# USB_stick.net
KiCad netlist of a schematic drawn in EAGLE
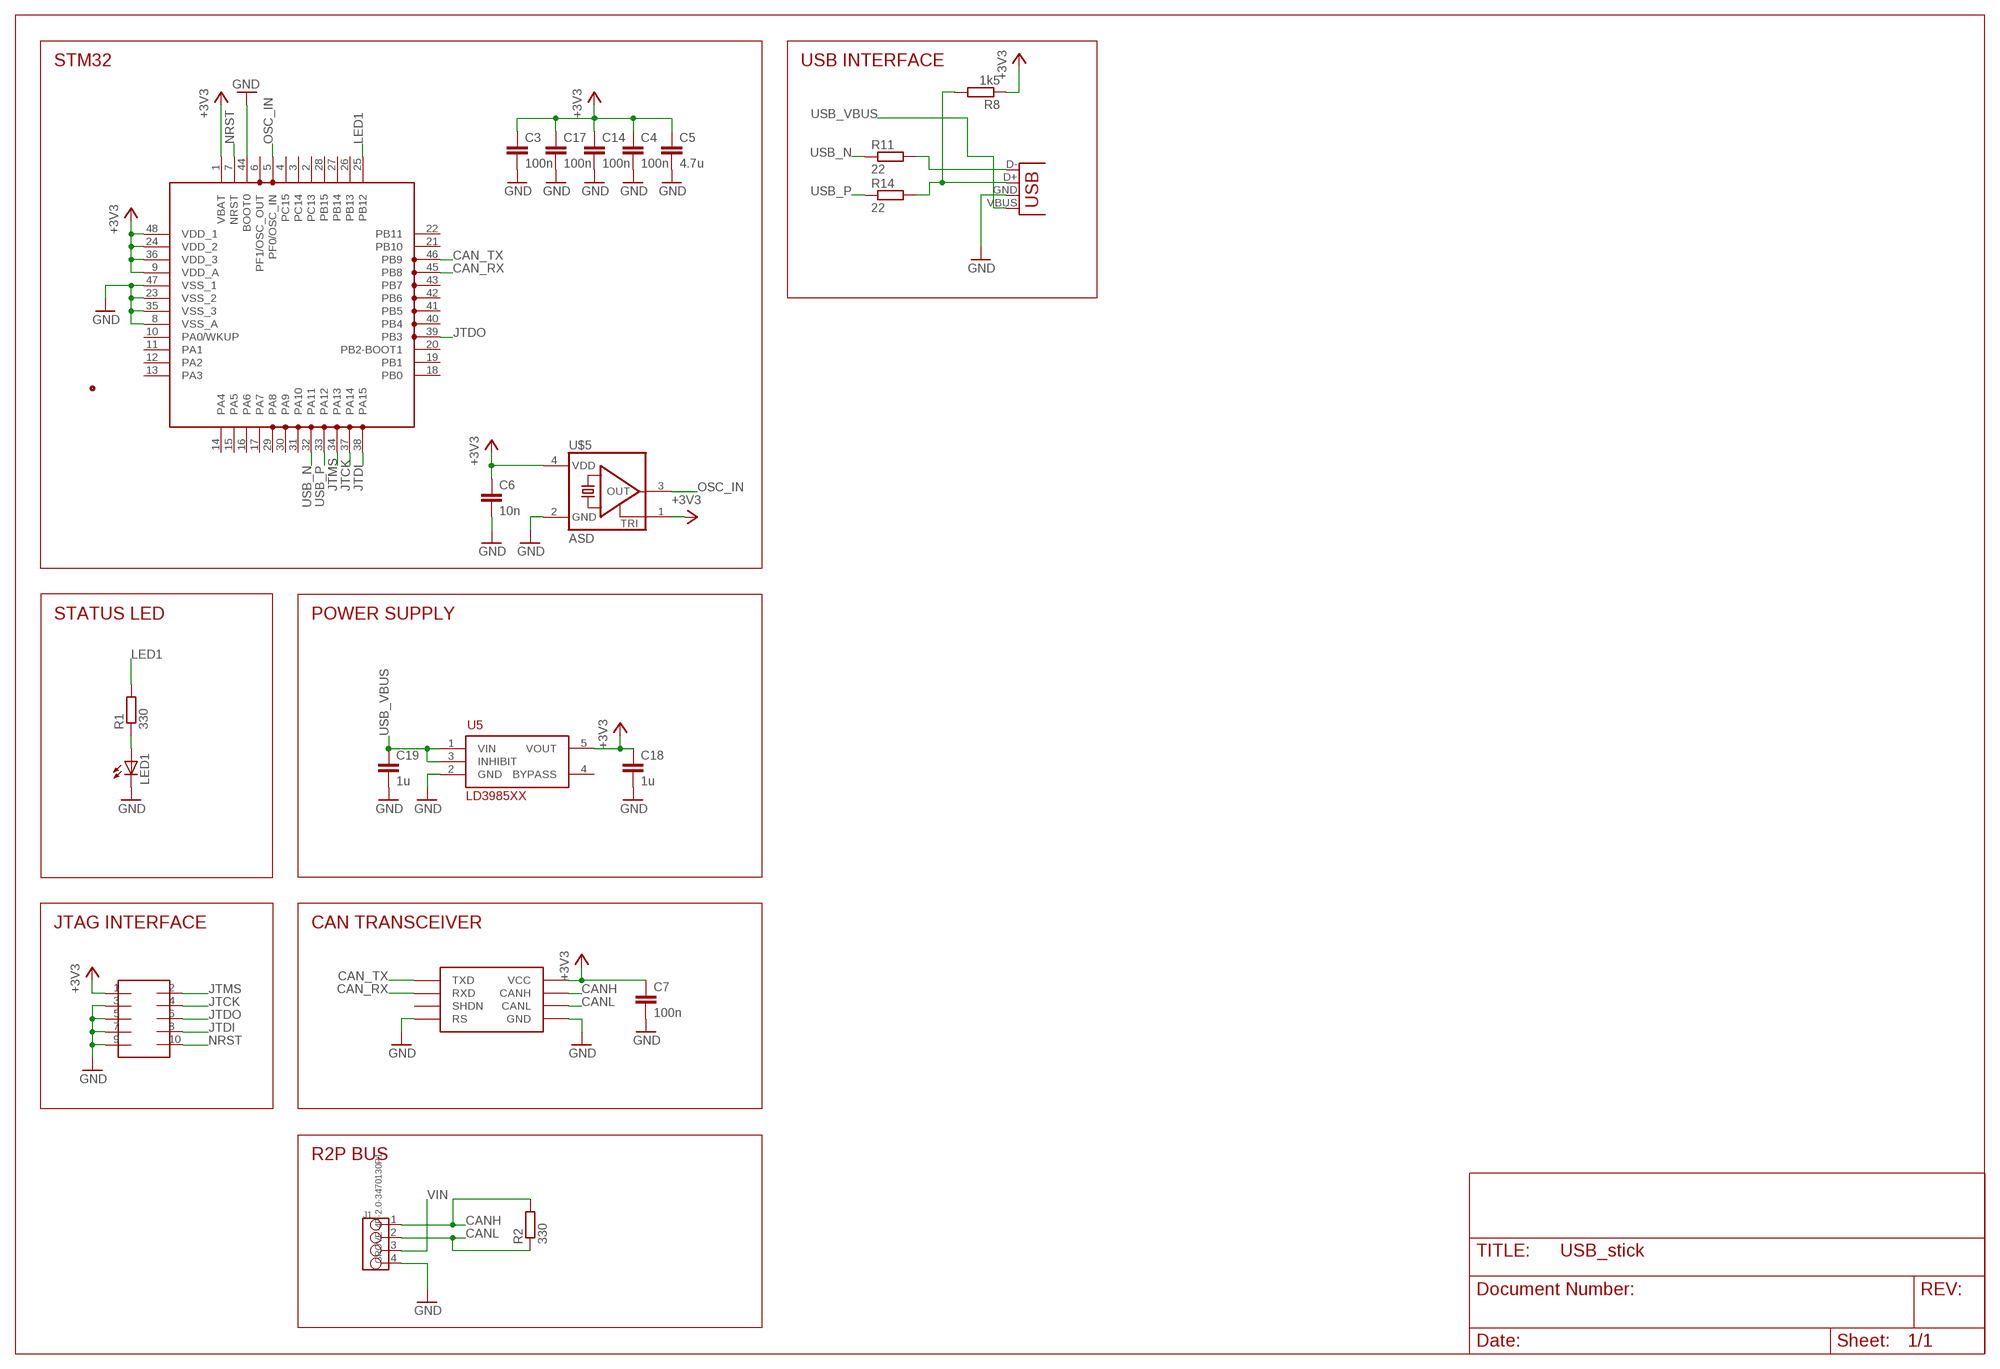
[diagram p0: schematic, sheet 1]

(export (version "E")
  (design (tool "Eeschema 10.0.6"))
  (components
    (comp (ref "C3")
      (value "100n")
      (footprint "eagle-import:C0603")
      (libsource (lib "eagle-import") (part "C-EUC0603"))
    )
    (comp (ref "C4")
      (value "100n")
      (footprint "eagle-import:C0603")
      (libsource (lib "eagle-import") (part "C-EUC0603"))
    )
    (comp (ref "C5")
      (value "4.7u")
      (footprint "eagle-import:C0805")
      (libsource (lib "eagle-import") (part "C-EUC0805"))
    )
    (comp (ref "C6")
      (value "10n")
      (footprint "eagle-import:C0603")
      (libsource (lib "eagle-import") (part "C-EUC0603"))
    )
    (comp (ref "C7")
      (value "100n")
      (footprint "eagle-import:C0603")
      (libsource (lib "eagle-import") (part "C-EUC0603"))
    )
    (comp (ref "C14")
      (value "100n")
      (footprint "eagle-import:C0603")
      (libsource (lib "eagle-import") (part "C-EUC0603"))
    )
    (comp (ref "C17")
      (value "100n")
      (footprint "eagle-import:C0603")
      (libsource (lib "eagle-import") (part "C-EUC0603"))
    )
    (comp (ref "C18")
      (value "1u")
      (footprint "eagle-import:C0603")
      (libsource (lib "eagle-import") (part "C-EUC0603"))
    )
    (comp (ref "C19")
      (value "1u")
      (footprint "eagle-import:C0603")
      (libsource (lib "eagle-import") (part "C-EUC0603"))
    )
    (comp (ref "J1")
      (value "GROVE-4P-2.0-3470130P1")
      (footprint "eagle-import:4P-2.0")
      (libsource (lib "eagle-import") (part "GROVE-4P-2.0-3470130P1"))
    )
    (comp (ref "JP1")
      (value "USB-A-H")
      (footprint "eagle-import:USB-A-H")
      (libsource (lib "eagle-import") (part "USB-A-H"))
    )
    (comp (ref "LED1")
      (value "LEDCHIPLED_0805")
      (footprint "eagle-import:CHIPLED_0805")
      (libsource (lib "eagle-import") (part "LEDCHIPLED_0805"))
    )
    (comp (ref "R1")
      (value "330")
      (footprint "eagle-import:R0603")
      (libsource (lib "eagle-import") (part "R0603"))
    )
    (comp (ref "R2")
      (value "330")
      (footprint "eagle-import:R0603")
      (libsource (lib "eagle-import") (part "R0603"))
    )
    (comp (ref "R8")
      (value "1k5")
      (footprint "eagle-import:R0603")
      (libsource (lib "eagle-import") (part "R0603"))
    )
    (comp (ref "R11")
      (value "22")
      (footprint "eagle-import:R0603")
      (libsource (lib "eagle-import") (part "R0603"))
    )
    (comp (ref "R14")
      (value "22")
      (footprint "eagle-import:R0603")
      (libsource (lib "eagle-import") (part "R0603"))
    )
    (comp (ref "SOT1")
      (value "MAX3051EKA")
      (footprint "eagle-import:SOT23-8L")
      (libsource (lib "eagle-import") (part "MAX3051EKA"))
    )
    (comp (ref "U$4")
      (value "FTSH-105TH")
      (footprint "eagle-import:FTSH-105-TH")
      (libsource (lib "eagle-import") (part "FTSH-105TH"))
    )
    (comp (ref "U$5")
      (value "ASD")
      (footprint "eagle-import:2.5X2")
      (libsource (lib "eagle-import") (part "ASD"))
    )
    (comp (ref "U$6")
      (value "STM32F303C")
      (footprint "eagle-import:LQFP48")
      (libsource (lib "eagle-import") (part "STM32F303C"))
    )
    (comp (ref "U5")
      (value "LD3985XX")
      (footprint "eagle-import:SOT23-5L")
      (libsource (lib "eagle-import") (part "LD3985XX"))
    )
  )
  (nets
    (net (code "1") (name "+3V3") (class "Default")
      (node (ref "C14") (pin "1") (pinfunction "1_1") (pintype "passive"))
      (node (ref "C17") (pin "1") (pinfunction "1_1") (pintype "passive"))
      (node (ref "C18") (pin "1") (pinfunction "1_1") (pintype "passive"))
      (node (ref "C3") (pin "1") (pinfunction "1_1") (pintype "passive"))
      (node (ref "C4") (pin "1") (pinfunction "1_1") (pintype "passive"))
      (node (ref "C5") (pin "1") (pinfunction "1_1") (pintype "passive"))
      (node (ref "C6") (pin "1") (pinfunction "1_1") (pintype "passive"))
      (node (ref "C7") (pin "1") (pinfunction "1_1") (pintype "passive"))
      (node (ref "R8") (pin "1") (pinfunction "1_1") (pintype "passive"))
      (node (ref "SOT1") (pin "3") (pinfunction "VCC_3") (pintype "bidirectional"))
      (node (ref "U$4") (pin "1") (pinfunction "P$1_1") (pintype "bidirectional"))
      (node (ref "U$5") (pin "1") (pinfunction "TRI_1") (pintype "input"))
      (node (ref "U$5") (pin "4") (pinfunction "VDD_4") (pintype "power_in"))
      (node (ref "U$6") (pin "1") (pinfunction "VBAT_1") (pintype "bidirectional"))
      (node (ref "U$6") (pin "24") (pinfunction "VDD_2_24") (pintype "bidirectional"))
      (node (ref "U$6") (pin "36") (pinfunction "VDD_3_36") (pintype "bidirectional"))
      (node (ref "U$6") (pin "48") (pinfunction "VDD_1_48") (pintype "bidirectional"))
      (node (ref "U$6") (pin "9") (pinfunction "VDD_A_9") (pintype "bidirectional"))
      (node (ref "U5") (pin "5") (pinfunction "VOUT_5") (pintype "bidirectional"))
    )
    (net (code "2") (name "/CANH") (class "Default")
      (node (ref "J1") (pin "1") (pinfunction "1_1") (pintype "bidirectional"))
      (node (ref "R2") (pin "2") (pinfunction "2_2") (pintype "passive"))
      (node (ref "SOT1") (pin "7") (pinfunction "CANH_7") (pintype "bidirectional"))
    )
    (net (code "3") (name "/CANL") (class "Default")
      (node (ref "J1") (pin "2") (pinfunction "2_2") (pintype "bidirectional"))
      (node (ref "R2") (pin "1") (pinfunction "1_1") (pintype "passive"))
      (node (ref "SOT1") (pin "6") (pinfunction "CANL_6") (pintype "bidirectional"))
    )
    (net (code "4") (name "/CAN_RX") (class "Default")
      (node (ref "SOT1") (pin "4") (pinfunction "RXD_4") (pintype "bidirectional"))
      (node (ref "U$6") (pin "45") (pinfunction "PB8_45") (pintype "bidirectional"))
    )
    (net (code "5") (name "/CAN_TX") (class "Default")
      (node (ref "SOT1") (pin "1") (pinfunction "TXD_1") (pintype "bidirectional"))
      (node (ref "U$6") (pin "46") (pinfunction "PB9_46") (pintype "bidirectional"))
    )
    (net (code "6") (name "/JTCK") (class "Default")
      (node (ref "U$4") (pin "4") (pinfunction "P$4_4") (pintype "bidirectional"))
      (node (ref "U$6") (pin "37") (pinfunction "PA14_37") (pintype "bidirectional"))
    )
    (net (code "7") (name "/JTDI") (class "Default")
      (node (ref "U$4") (pin "8") (pinfunction "P$8_8") (pintype "bidirectional"))
      (node (ref "U$6") (pin "38") (pinfunction "PA15_38") (pintype "bidirectional"))
    )
    (net (code "8") (name "/JTDO") (class "Default")
      (node (ref "U$4") (pin "6") (pinfunction "P$6_6") (pintype "bidirectional"))
      (node (ref "U$6") (pin "39") (pinfunction "PB3_39") (pintype "bidirectional"))
    )
    (net (code "9") (name "/JTMS") (class "Default")
      (node (ref "U$4") (pin "2") (pinfunction "P$2_2") (pintype "bidirectional"))
      (node (ref "U$6") (pin "34") (pinfunction "PA13_34") (pintype "bidirectional"))
    )
    (net (code "10") (name "/LED1") (class "Default")
      (node (ref "R1") (pin "2") (pinfunction "2_2") (pintype "passive"))
      (node (ref "U$6") (pin "25") (pinfunction "PB12_25") (pintype "bidirectional"))
    )
    (net (code "11") (name "/NRST") (class "Default")
      (node (ref "U$4") (pin "10") (pinfunction "P$10_10") (pintype "bidirectional"))
      (node (ref "U$6") (pin "7") (pinfunction "NRST_7") (pintype "bidirectional"))
    )
    (net (code "12") (name "/OSC_IN") (class "Default")
      (node (ref "U$5") (pin "3") (pinfunction "OUT_3") (pintype "output"))
      (node (ref "U$6") (pin "5") (pinfunction "PF0/OSC_IN_5") (pintype "bidirectional"))
    )
    (net (code "13") (name "/USB_N") (class "Default")
      (node (ref "R11") (pin "1") (pinfunction "1_1") (pintype "passive"))
      (node (ref "U$6") (pin "32") (pinfunction "PA11_32") (pintype "bidirectional"))
    )
    (net (code "14") (name "/USB_P") (class "Default")
      (node (ref "R14") (pin "1") (pinfunction "1_1") (pintype "passive"))
      (node (ref "U$6") (pin "33") (pinfunction "PA12_33") (pintype "bidirectional"))
    )
    (net (code "15") (name "/USB_VBUS") (class "Default")
      (node (ref "C19") (pin "1") (pinfunction "1_1") (pintype "passive"))
      (node (ref "JP1") (pin "VBUS") (pinfunction "GND_VBUS") (pintype "bidirectional"))
      (node (ref "U5") (pin "1") (pinfunction "VIN_1") (pintype "bidirectional"))
      (node (ref "U5") (pin "3") (pinfunction "INHIBIT_3") (pintype "bidirectional"))
    )
    (net (code "16") (name "/VIN") (class "Default")
      (node (ref "J1") (pin "3") (pinfunction "3_3") (pintype "bidirectional"))
    )
    (net (code "17") (name "GND") (class "Default")
      (node (ref "C14") (pin "2") (pinfunction "2_2") (pintype "passive"))
      (node (ref "C17") (pin "2") (pinfunction "2_2") (pintype "passive"))
      (node (ref "C18") (pin "2") (pinfunction "2_2") (pintype "passive"))
      (node (ref "C19") (pin "2") (pinfunction "2_2") (pintype "passive"))
      (node (ref "C3") (pin "2") (pinfunction "2_2") (pintype "passive"))
      (node (ref "C4") (pin "2") (pinfunction "2_2") (pintype "passive"))
      (node (ref "C5") (pin "2") (pinfunction "2_2") (pintype "passive"))
      (node (ref "C6") (pin "2") (pinfunction "2_2") (pintype "passive"))
      (node (ref "C7") (pin "2") (pinfunction "2_2") (pintype "passive"))
      (node (ref "J1") (pin "4") (pinfunction "4_4") (pintype "bidirectional"))
      (node (ref "JP1") (pin "GND") (pinfunction "VBUS_GND") (pintype "bidirectional"))
      (node (ref "LED1") (pin "C") (pinfunction "C_C") (pintype "passive"))
      (node (ref "SOT1") (pin "2") (pinfunction "GND_2") (pintype "bidirectional"))
      (node (ref "SOT1") (pin "8") (pinfunction "RS_8") (pintype "bidirectional"))
      (node (ref "U$4") (pin "3") (pinfunction "P$3_3") (pintype "bidirectional"))
      (node (ref "U$4") (pin "5") (pinfunction "P$5_5") (pintype "bidirectional"))
      (node (ref "U$4") (pin "7") (pinfunction "P$7_7") (pintype "bidirectional"))
      (node (ref "U$4") (pin "9") (pinfunction "P$9_9") (pintype "bidirectional"))
      (node (ref "U$5") (pin "2") (pinfunction "GND_2") (pintype "power_in"))
      (node (ref "U$6") (pin "23") (pinfunction "VSS_2_23") (pintype "bidirectional"))
      (node (ref "U$6") (pin "35") (pinfunction "VSS_3_35") (pintype "bidirectional"))
      (node (ref "U$6") (pin "44") (pinfunction "BOOT0_44") (pintype "bidirectional"))
      (node (ref "U$6") (pin "47") (pinfunction "VSS_1_47") (pintype "bidirectional"))
      (node (ref "U$6") (pin "8") (pinfunction "VSS_A_8") (pintype "bidirectional"))
      (node (ref "U5") (pin "2") (pinfunction "GND_2") (pintype "bidirectional"))
    )
    (net (code "18") (name "Net-(JP1-D+)") (class "Default")
      (node (ref "JP1") (pin "D-") (pinfunction "D+_D-") (pintype "bidirectional"))
      (node (ref "R11") (pin "2") (pinfunction "2_2") (pintype "passive"))
    )
    (net (code "19") (name "Net-(JP1-D-)") (class "Default")
      (node (ref "JP1") (pin "D+") (pinfunction "D-_D+") (pintype "bidirectional"))
      (node (ref "R14") (pin "2") (pinfunction "2_2") (pintype "passive"))
      (node (ref "R8") (pin "2") (pinfunction "2_2") (pintype "passive"))
    )
    (net (code "20") (name "Net-(LED1-PadA)") (class "Default")
      (node (ref "LED1") (pin "A") (pinfunction "A_A") (pintype "passive"))
      (node (ref "R1") (pin "1") (pinfunction "1_1") (pintype "passive"))
    )
    (net (code "21") (name "unconnected-(SOT1-SHDN-Pad5)") (class "Default")
      (node (ref "SOT1") (pin "5") (pinfunction "SHDN_5") (pintype "bidirectional"))
    )
    (net (code "22") (name "unconnected-(U$6-PA0{slash}WKUP-Pad10)") (class "Default")
      (node (ref "U$6") (pin "10") (pinfunction "PA0/WKUP_10") (pintype "bidirectional"))
    )
    (net (code "23") (name "unconnected-(U$6-PA1-Pad11)") (class "Default")
      (node (ref "U$6") (pin "11") (pinfunction "PA1_11") (pintype "bidirectional"))
    )
    (net (code "24") (name "unconnected-(U$6-PA2-Pad12)") (class "Default")
      (node (ref "U$6") (pin "12") (pinfunction "PA2_12") (pintype "bidirectional"))
    )
    (net (code "25") (name "unconnected-(U$6-PA3-Pad13)") (class "Default")
      (node (ref "U$6") (pin "13") (pinfunction "PA3_13") (pintype "bidirectional"))
    )
    (net (code "26") (name "unconnected-(U$6-PA4-Pad14)") (class "Default")
      (node (ref "U$6") (pin "14") (pinfunction "PA4_14") (pintype "bidirectional"))
    )
    (net (code "27") (name "unconnected-(U$6-PA5-Pad15)") (class "Default")
      (node (ref "U$6") (pin "15") (pinfunction "PA5_15") (pintype "bidirectional"))
    )
    (net (code "28") (name "unconnected-(U$6-PA6-Pad16)") (class "Default")
      (node (ref "U$6") (pin "16") (pinfunction "PA6_16") (pintype "bidirectional"))
    )
    (net (code "29") (name "unconnected-(U$6-PA7-Pad17)") (class "Default")
      (node (ref "U$6") (pin "17") (pinfunction "PA7_17") (pintype "bidirectional"))
    )
    (net (code "30") (name "unconnected-(U$6-PA8-Pad29)") (class "Default")
      (node (ref "U$6") (pin "29") (pinfunction "PA8_29") (pintype "bidirectional"))
    )
    (net (code "31") (name "unconnected-(U$6-PA9-Pad30)") (class "Default")
      (node (ref "U$6") (pin "30") (pinfunction "PA9_30") (pintype "bidirectional"))
    )
    (net (code "32") (name "unconnected-(U$6-PA10-Pad31)") (class "Default")
      (node (ref "U$6") (pin "31") (pinfunction "PA10_31") (pintype "bidirectional"))
    )
    (net (code "33") (name "unconnected-(U$6-PB0-Pad18)") (class "Default")
      (node (ref "U$6") (pin "18") (pinfunction "PB0_18") (pintype "bidirectional"))
    )
    (net (code "34") (name "unconnected-(U$6-PB1-Pad19)") (class "Default")
      (node (ref "U$6") (pin "19") (pinfunction "PB1_19") (pintype "bidirectional"))
    )
    (net (code "35") (name "unconnected-(U$6-PB2-BOOT1-Pad20)") (class "Default")
      (node (ref "U$6") (pin "20") (pinfunction "PB2-BOOT1_20") (pintype "bidirectional"))
    )
    (net (code "36") (name "unconnected-(U$6-PB4-Pad40)") (class "Default")
      (node (ref "U$6") (pin "40") (pinfunction "PB4_40") (pintype "bidirectional"))
    )
    (net (code "37") (name "unconnected-(U$6-PB5-Pad41)") (class "Default")
      (node (ref "U$6") (pin "41") (pinfunction "PB5_41") (pintype "bidirectional"))
    )
    (net (code "38") (name "unconnected-(U$6-PB6-Pad42)") (class "Default")
      (node (ref "U$6") (pin "42") (pinfunction "PB6_42") (pintype "bidirectional"))
    )
    (net (code "39") (name "unconnected-(U$6-PB7-Pad43)") (class "Default")
      (node (ref "U$6") (pin "43") (pinfunction "PB7_43") (pintype "bidirectional"))
    )
    (net (code "40") (name "unconnected-(U$6-PB10-Pad21)") (class "Default")
      (node (ref "U$6") (pin "21") (pinfunction "PB10_21") (pintype "bidirectional"))
    )
    (net (code "41") (name "unconnected-(U$6-PB11-Pad22)") (class "Default")
      (node (ref "U$6") (pin "22") (pinfunction "PB11_22") (pintype "bidirectional"))
    )
    (net (code "42") (name "unconnected-(U$6-PB13-Pad26)") (class "Default")
      (node (ref "U$6") (pin "26") (pinfunction "PB13_26") (pintype "bidirectional"))
    )
    (net (code "43") (name "unconnected-(U$6-PB14-Pad27)") (class "Default")
      (node (ref "U$6") (pin "27") (pinfunction "PB14_27") (pintype "bidirectional"))
    )
    (net (code "44") (name "unconnected-(U$6-PB15-Pad28)") (class "Default")
      (node (ref "U$6") (pin "28") (pinfunction "PB15_28") (pintype "bidirectional"))
    )
    (net (code "45") (name "unconnected-(U$6-PC13-Pad2)") (class "Default")
      (node (ref "U$6") (pin "2") (pinfunction "PC13_2") (pintype "bidirectional"))
    )
    (net (code "46") (name "unconnected-(U$6-PC14-Pad3)") (class "Default")
      (node (ref "U$6") (pin "3") (pinfunction "PC14_3") (pintype "bidirectional"))
    )
    (net (code "47") (name "unconnected-(U$6-PC15-Pad4)") (class "Default")
      (node (ref "U$6") (pin "4") (pinfunction "PC15_4") (pintype "bidirectional"))
    )
    (net (code "48") (name "unconnected-(U$6-PF1{slash}OSC_OUT-Pad6)") (class "Default")
      (node (ref "U$6") (pin "6") (pinfunction "PF1/OSC_OUT_6") (pintype "bidirectional"))
    )
    (net (code "49") (name "unconnected-(U5-BYPASS-Pad4)") (class "Default")
      (node (ref "U5") (pin "4") (pinfunction "BYPASS_4") (pintype "bidirectional"))
    )
  )
)
